# Solenoid_Driver.net
KiCad netlist of a schematic drawn in Altium Designer
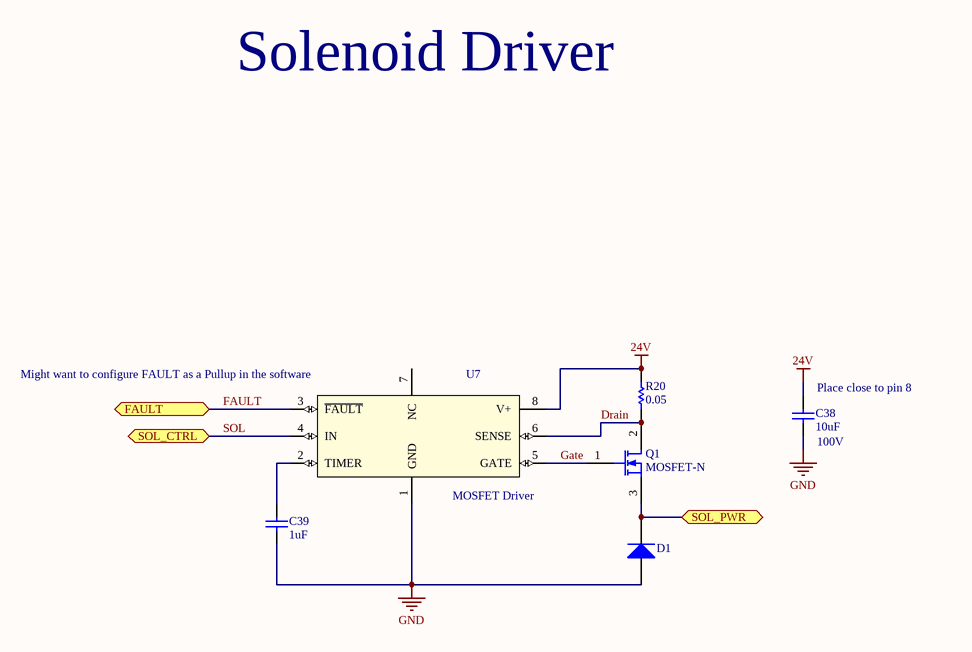
[diagram p0: Solenoid_Driver.SchDoc]

(export (version "E")
  (design (tool "Eeschema 10.0.6"))
  (components
    (comp (ref "C38")
      (value "10uF")
      (footprint "1206")
      (description "Capacitor")
      (fields (field (name "VOLTAGE") "100V") (field (name "Comment") "Cap"))
      (libsource (lib "Miscellaneous Devices") (part "Cap"))
    )
    (comp (ref "C39")
      (value "1uF")
      (footprint "CAP_0603")
      (description "Capacitor")
      (fields (field (name "Comment") "Cap"))
      (libsource (lib "Miscellaneous Devices") (part "Cap"))
    )
    (comp (ref "D1")
      (value "Diode")
      (footprint "SMC")
      (description "Default Diode")
      (libsource (lib "Miscellaneous Devices") (part "Diode"))
    )
    (comp (ref "Q1")
      (value "MOSFET-N")
      (footprint "DPAK2")
      (description "N-Channel MOSFET")
      (libsource (lib "Miscellaneous Devices") (part "MOSFET-N"))
    )
    (comp (ref "R20")
      (value "0.05")
      (footprint "RES_0603")
      (description "Resistor")
      (fields (field (name "Comment") "Res1"))
      (libsource (lib "Miscellaneous Devices") (part "Res1"))
    )
    (comp (ref "U7")
      (value "MOSFET Driver")
      (footprint "PSO-8")
      (fields (field (name "MANUFACTURER_PART_NUMBER") "lt1910es8#pbf"))
      (libsource (lib "LaunchyRIOComponents") (part "LT1910ES8#PBF"))
    )
  )
  (nets
    (net (code "1") (name "/Drain") (class "Default")
      (node (ref "Q1") (pin "2") (pinfunction "D_2") (pintype "passive"))
      (node (ref "R20") (pin "1") (pinfunction "1_1") (pintype "passive"))
      (node (ref "U7") (pin "6") (pinfunction "SENSE_6") (pintype "bidirectional"))
    )
    (net (code "2") (name "/FAULT") (class "Default")
      (node (ref "U7") (pin "3") (pinfunction "~{FAULT}_3") (pintype "bidirectional"))
    )
    (net (code "3") (name "/Gate") (class "Default")
      (node (ref "Q1") (pin "1") (pinfunction "G_1") (pintype "passive"))
      (node (ref "U7") (pin "5") (pinfunction "GATE_5") (pintype "bidirectional"))
    )
    (net (code "4") (name "/SOL") (class "Default")
      (node (ref "U7") (pin "4") (pinfunction "IN_4") (pintype "bidirectional"))
    )
    (net (code "5") (name "/SOL_PWR") (class "Default")
      (node (ref "D1") (pin "2") (pinfunction "K_2") (pintype "passive"))
      (node (ref "Q1") (pin "3") (pinfunction "S_3") (pintype "passive"))
    )
    (net (code "6") (name "24V") (class "Default")
      (node (ref "C38") (pin "2") (pinfunction "2_2") (pintype "passive"))
      (node (ref "R20") (pin "2") (pinfunction "2_2") (pintype "passive"))
      (node (ref "U7") (pin "8") (pinfunction "V+_8") (pintype "power_in"))
    )
    (net (code "7") (name "GND") (class "Default")
      (node (ref "C38") (pin "1") (pinfunction "1_1") (pintype "passive"))
      (node (ref "C39") (pin "1") (pinfunction "1_1") (pintype "passive"))
      (node (ref "D1") (pin "1") (pinfunction "A_1") (pintype "passive"))
      (node (ref "U7") (pin "1") (pinfunction "GND_1") (pintype "power_in"))
    )
    (net (code "8") (name "Net-(U7-TIMER)") (class "Default")
      (node (ref "C39") (pin "2") (pinfunction "2_2") (pintype "passive"))
      (node (ref "U7") (pin "2") (pinfunction "TIMER_2") (pintype "bidirectional"))
    )
    (net (code "9") (name "unconnected-(U7-NC-Pad7)") (class "Default")
      (node (ref "U7") (pin "7") (pinfunction "NC_7") (pintype "passive"))
    )
  )
)
